# lampada_rev4.net
KiCad netlist of a schematic drawn in EAGLE
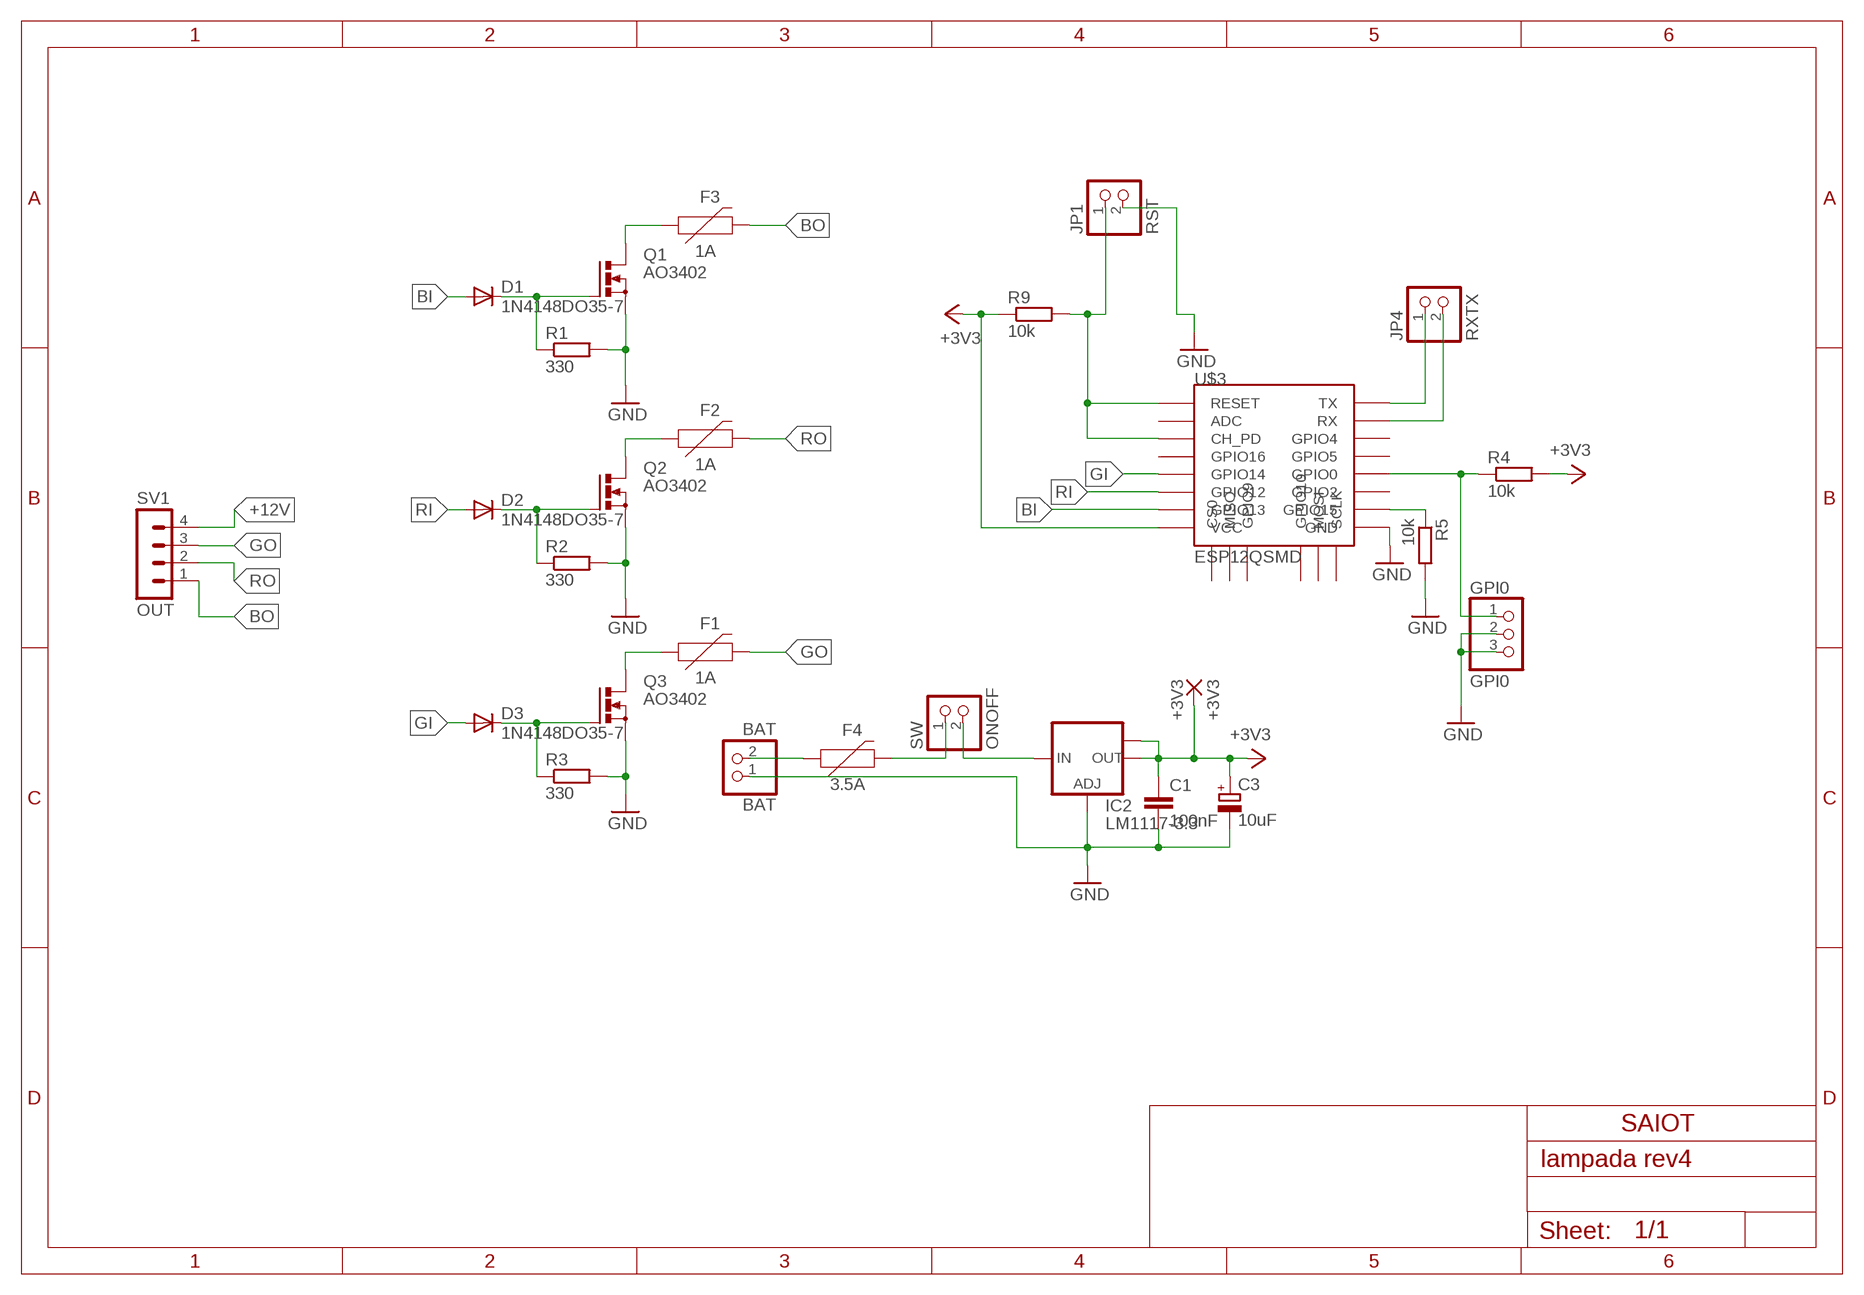
[diagram p0: schematic, sheet 1]

(export (version "E")
  (design (tool "Eeschema 10.0.6"))
  (components
    (comp (ref "+3V3")
      (value "+3V3")
      (footprint "eagle-import:2,15_1,0")
      (libsource (lib "eagle-import") (part "2,15/1,0"))
    )
    (comp (ref "BAT")
      (value "BAT")
      (footprint "eagle-import:1X02")
      (libsource (lib "eagle-import") (part "PINHD-1X2"))
    )
    (comp (ref "C1")
      (value "100nF")
      (footprint "eagle-import:C050-024X044")
      (libsource (lib "eagle-import") (part "C-EU050-024X044"))
    )
    (comp (ref "C3")
      (value "10uF")
      (footprint "eagle-import:E2,5-7")
      (libsource (lib "eagle-import") (part "CPOL-EUE2.5-7"))
    )
    (comp (ref "D1")
      (value "1N4148DO35-7")
      (footprint "eagle-import:DO35-7")
      (libsource (lib "eagle-import") (part "1N4148DO35-7"))
    )
    (comp (ref "D2")
      (value "1N4148DO35-7")
      (footprint "eagle-import:DO35-7")
      (libsource (lib "eagle-import") (part "1N4148DO35-7"))
    )
    (comp (ref "D3")
      (value "1N4148DO35-7")
      (footprint "eagle-import:DO35-7")
      (libsource (lib "eagle-import") (part "1N4148DO35-7"))
    )
    (comp (ref "F1")
      (value "1A")
      (footprint "eagle-import:0805")
      (libsource (lib "eagle-import") (part "PPTC_6V500MA"))
    )
    (comp (ref "F2")
      (value "1A")
      (footprint "eagle-import:0805")
      (libsource (lib "eagle-import") (part "PPTC_6V500MA"))
    )
    (comp (ref "F3")
      (value "1A")
      (footprint "eagle-import:0805")
      (libsource (lib "eagle-import") (part "PPTC_6V500MA"))
    )
    (comp (ref "F4")
      (value "3.5A")
      (footprint "eagle-import:0805")
      (libsource (lib "eagle-import") (part "PPTC_6V500MA"))
    )
    (comp (ref "GPI0")
      (value "GPI0")
      (footprint "eagle-import:1X03")
      (libsource (lib "eagle-import") (part "PINHD-1X3"))
    )
    (comp (ref "IC2")
      (value "LM1117-3.3")
      (footprint "eagle-import:SOT223")
      (libsource (lib "eagle-import") (part "LM1117IMPX-ADJ"))
    )
    (comp (ref "JP1")
      (value "RST")
      (footprint "eagle-import:1X02")
      (libsource (lib "eagle-import") (part "PINHD-1X2"))
    )
    (comp (ref "JP4")
      (value "RXTX")
      (footprint "eagle-import:1X02")
      (libsource (lib "eagle-import") (part "PINHD-1X2"))
    )
    (comp (ref "Q1")
      (value "AO3402")
      (footprint "eagle-import:SOT-23")
      (libsource (lib "eagle-import") (part "IRLML6344"))
    )
    (comp (ref "Q2")
      (value "AO3402")
      (footprint "eagle-import:SOT-23")
      (libsource (lib "eagle-import") (part "IRLML6344"))
    )
    (comp (ref "Q3")
      (value "AO3402")
      (footprint "eagle-import:SOT-23")
      (libsource (lib "eagle-import") (part "IRLML6344"))
    )
    (comp (ref "R1")
      (value "330")
      (footprint "eagle-import:0204_7")
      (libsource (lib "eagle-import") (part "R-EU_0204/7"))
    )
    (comp (ref "R2")
      (value "330")
      (footprint "eagle-import:0204_7")
      (libsource (lib "eagle-import") (part "R-EU_0204/7"))
    )
    (comp (ref "R3")
      (value "330")
      (footprint "eagle-import:0204_7")
      (libsource (lib "eagle-import") (part "R-EU_0204/7"))
    )
    (comp (ref "R4")
      (value "10k")
      (footprint "eagle-import:0204_7")
      (libsource (lib "eagle-import") (part "R-EU_0204/7"))
    )
    (comp (ref "R5")
      (value "10k")
      (footprint "eagle-import:0204_7")
      (libsource (lib "eagle-import") (part "R-EU_0204/7"))
    )
    (comp (ref "R9")
      (value "10k")
      (footprint "eagle-import:0204_7")
      (libsource (lib "eagle-import") (part "R-EU_0204/7"))
    )
    (comp (ref "SV1")
      (value "OUT")
      (footprint "eagle-import:MA04-1")
      (libsource (lib "eagle-import") (part "MA04-1"))
    )
    (comp (ref "SW")
      (value "ONOFF")
      (footprint "eagle-import:1X02")
      (libsource (lib "eagle-import") (part "PINHD-1X2"))
    )
    (comp (ref "U$3")
      (value "ESP12QSMD")
      (footprint "eagle-import:ESP12QSMD")
      (libsource (lib "eagle-import") (part "ESP12QSMD"))
    )
  )
  (nets
    (net (code "1") (name "+3V3") (class "Default")
      (node (ref "+3V3") (pin "1") (pinfunction "P_1") (pintype "passive"))
      (node (ref "C1") (pin "1") (pinfunction "1_1") (pintype "passive"))
      (node (ref "C3") (pin "+") (pinfunction "+_+") (pintype "passive"))
      (node (ref "IC2") (pin "2") (pinfunction "OUT_2") (pintype "passive"))
      (node (ref "IC2") (pin "TAB") (pinfunction "OUT1_TAB") (pintype "passive"))
      (node (ref "R4") (pin "2") (pinfunction "2_2") (pintype "passive"))
      (node (ref "R9") (pin "1") (pinfunction "1_1") (pintype "passive"))
      (node (ref "U$3") (pin "VCC") (pinfunction "VCC_VCC") (pintype "bidirectional"))
    )
    (net (code "2") (name "+12V") (class "Default")
      (node (ref "IC2") (pin "3") (pinfunction "IN_3") (pintype "input"))
      (node (ref "SV1") (pin "4") (pinfunction "4_4") (pintype "passive"))
      (node (ref "SW") (pin "2") (pinfunction "2_2") (pintype "passive"))
    )
    (net (code "3") (name "BI") (class "Default")
      (node (ref "D1") (pin "A") (pinfunction "A_A") (pintype "passive"))
      (node (ref "U$3") (pin "GPIO13") (pinfunction "GPIO13_GPIO13") (pintype "bidirectional"))
    )
    (net (code "4") (name "BO") (class "Default")
      (node (ref "F3") (pin "2") (pinfunction "2_2") (pintype "bidirectional"))
      (node (ref "SV1") (pin "1") (pinfunction "1_1") (pintype "passive"))
    )
    (net (code "5") (name "GI") (class "Default")
      (node (ref "D3") (pin "A") (pinfunction "A_A") (pintype "passive"))
      (node (ref "U$3") (pin "GPIO14") (pinfunction "GPIO14_GPIO14") (pintype "bidirectional"))
    )
    (net (code "6") (name "GND") (class "Default")
      (node (ref "BAT") (pin "1") (pinfunction "1_1") (pintype "passive"))
      (node (ref "C1") (pin "2") (pinfunction "2_2") (pintype "passive"))
      (node (ref "C3") (pin "-") (pinfunction "-_-") (pintype "passive"))
      (node (ref "GPI0") (pin "2") (pinfunction "2_2") (pintype "passive"))
      (node (ref "GPI0") (pin "3") (pinfunction "3_3") (pintype "passive"))
      (node (ref "IC2") (pin "1") (pinfunction "ADJ_1") (pintype "input"))
      (node (ref "JP1") (pin "2") (pinfunction "2_2") (pintype "passive"))
      (node (ref "Q1") (pin "P2") (pinfunction "S_P2") (pintype "passive"))
      (node (ref "Q2") (pin "P2") (pinfunction "S_P2") (pintype "passive"))
      (node (ref "Q3") (pin "P2") (pinfunction "S_P2") (pintype "passive"))
      (node (ref "R1") (pin "2") (pinfunction "2_2") (pintype "passive"))
      (node (ref "R2") (pin "2") (pinfunction "2_2") (pintype "passive"))
      (node (ref "R3") (pin "2") (pinfunction "2_2") (pintype "passive"))
      (node (ref "R5") (pin "2") (pinfunction "2_2") (pintype "passive"))
      (node (ref "U$3") (pin "GND") (pinfunction "GND_GND") (pintype "bidirectional"))
    )
    (net (code "7") (name "GO") (class "Default")
      (node (ref "F1") (pin "2") (pinfunction "2_2") (pintype "bidirectional"))
      (node (ref "SV1") (pin "3") (pinfunction "3_3") (pintype "passive"))
    )
    (net (code "8") (name "Net-(BAT-Pad2)") (class "Default")
      (node (ref "BAT") (pin "2") (pinfunction "2_2") (pintype "passive"))
      (node (ref "F4") (pin "1") (pinfunction "1_1") (pintype "bidirectional"))
    )
    (net (code "9") (name "Net-(F4-Pad2)") (class "Default")
      (node (ref "F4") (pin "2") (pinfunction "2_2") (pintype "bidirectional"))
      (node (ref "SW") (pin "1") (pinfunction "1_1") (pintype "passive"))
    )
    (net (code "10") (name "Net-(GPI0-Pad1)") (class "Default")
      (node (ref "GPI0") (pin "1") (pinfunction "1_1") (pintype "passive"))
      (node (ref "R4") (pin "1") (pinfunction "1_1") (pintype "passive"))
      (node (ref "U$3") (pin "GPIO0") (pinfunction "GPIO0_GPIO0") (pintype "bidirectional"))
    )
    (net (code "11") (name "Net-(JP1-Pad1)") (class "Default")
      (node (ref "JP1") (pin "1") (pinfunction "1_1") (pintype "passive"))
      (node (ref "R9") (pin "2") (pinfunction "2_2") (pintype "passive"))
      (node (ref "U$3") (pin "CH_PD") (pinfunction "CH_PD_CH_PD") (pintype "bidirectional"))
      (node (ref "U$3") (pin "RESET") (pinfunction "RESET_RESET") (pintype "bidirectional"))
    )
    (net (code "12") (name "Net-(JP4-Pad1)") (class "Default")
      (node (ref "JP4") (pin "1") (pinfunction "1_1") (pintype "passive"))
      (node (ref "U$3") (pin "TX") (pinfunction "TX_TX") (pintype "bidirectional"))
    )
    (net (code "13") (name "Net-(JP4-Pad2)") (class "Default")
      (node (ref "JP4") (pin "2") (pinfunction "2_2") (pintype "passive"))
      (node (ref "U$3") (pin "RX") (pinfunction "RX_RX") (pintype "bidirectional"))
    )
    (net (code "14") (name "Net-(Q1-D)") (class "Default")
      (node (ref "F3") (pin "1") (pinfunction "1_1") (pintype "bidirectional"))
      (node (ref "Q1") (pin "P3") (pinfunction "D_P3") (pintype "passive"))
    )
    (net (code "15") (name "Net-(Q1-G)") (class "Default")
      (node (ref "D1") (pin "C") (pinfunction "C_C") (pintype "passive"))
      (node (ref "Q1") (pin "P1") (pinfunction "G_P1") (pintype "passive"))
      (node (ref "R1") (pin "1") (pinfunction "1_1") (pintype "passive"))
    )
    (net (code "16") (name "Net-(Q2-D)") (class "Default")
      (node (ref "F2") (pin "1") (pinfunction "1_1") (pintype "bidirectional"))
      (node (ref "Q2") (pin "P3") (pinfunction "D_P3") (pintype "passive"))
    )
    (net (code "17") (name "Net-(Q2-G)") (class "Default")
      (node (ref "D2") (pin "C") (pinfunction "C_C") (pintype "passive"))
      (node (ref "Q2") (pin "P1") (pinfunction "G_P1") (pintype "passive"))
      (node (ref "R2") (pin "1") (pinfunction "1_1") (pintype "passive"))
    )
    (net (code "18") (name "Net-(Q3-D)") (class "Default")
      (node (ref "F1") (pin "1") (pinfunction "1_1") (pintype "bidirectional"))
      (node (ref "Q3") (pin "P3") (pinfunction "D_P3") (pintype "passive"))
    )
    (net (code "19") (name "Net-(Q3-G)") (class "Default")
      (node (ref "D3") (pin "C") (pinfunction "C_C") (pintype "passive"))
      (node (ref "Q3") (pin "P1") (pinfunction "G_P1") (pintype "passive"))
      (node (ref "R3") (pin "1") (pinfunction "1_1") (pintype "passive"))
    )
    (net (code "20") (name "Net-(R5-Pad1)") (class "Default")
      (node (ref "R5") (pin "1") (pinfunction "1_1") (pintype "passive"))
      (node (ref "U$3") (pin "GPIO15") (pinfunction "GPIO15_GPIO15") (pintype "bidirectional"))
    )
    (net (code "21") (name "RI") (class "Default")
      (node (ref "D2") (pin "A") (pinfunction "A_A") (pintype "passive"))
      (node (ref "U$3") (pin "GPIO12") (pinfunction "GPIO12_GPIO12") (pintype "bidirectional"))
    )
    (net (code "22") (name "RO") (class "Default")
      (node (ref "F2") (pin "2") (pinfunction "2_2") (pintype "bidirectional"))
      (node (ref "SV1") (pin "2") (pinfunction "2_2") (pintype "passive"))
    )
    (net (code "23") (name "unconnected-(U$3-PadADC)") (class "Default")
      (node (ref "U$3") (pin "ADC") (pinfunction "ADC_ADC") (pintype "bidirectional"))
    )
    (net (code "24") (name "unconnected-(U$3-PadCS0)") (class "Default")
      (node (ref "U$3") (pin "CS0") (pinfunction "CS0_CS0") (pintype "bidirectional"))
    )
    (net (code "25") (name "unconnected-(U$3-PadGPIO2)") (class "Default")
      (node (ref "U$3") (pin "GPIO2") (pinfunction "GPIO2_GPIO2") (pintype "bidirectional"))
    )
    (net (code "26") (name "unconnected-(U$3-PadGPIO4)") (class "Default")
      (node (ref "U$3") (pin "GPIO4") (pinfunction "GPIO4_GPIO4") (pintype "bidirectional"))
    )
    (net (code "27") (name "unconnected-(U$3-PadGPIO5)") (class "Default")
      (node (ref "U$3") (pin "GPIO5") (pinfunction "GPIO5_GPIO5") (pintype "bidirectional"))
    )
    (net (code "28") (name "unconnected-(U$3-PadGPIO9)") (class "Default")
      (node (ref "U$3") (pin "GPIO9") (pinfunction "GPIO9_GPIO9") (pintype "bidirectional"))
    )
    (net (code "29") (name "unconnected-(U$3-PadGPIO10)") (class "Default")
      (node (ref "U$3") (pin "GPIO10") (pinfunction "GPIO10_GPIO10") (pintype "bidirectional"))
    )
    (net (code "30") (name "unconnected-(U$3-PadGPIO16)") (class "Default")
      (node (ref "U$3") (pin "GPIO16") (pinfunction "GPIO16_GPIO16") (pintype "bidirectional"))
    )
    (net (code "31") (name "unconnected-(U$3-PadMISO)") (class "Default")
      (node (ref "U$3") (pin "MISO") (pinfunction "MISO_MISO") (pintype "bidirectional"))
    )
    (net (code "32") (name "unconnected-(U$3-PadMOSI)") (class "Default")
      (node (ref "U$3") (pin "MOSI") (pinfunction "MOSI_MOSI") (pintype "bidirectional"))
    )
    (net (code "33") (name "unconnected-(U$3-PadSCLK)") (class "Default")
      (node (ref "U$3") (pin "SCLK") (pinfunction "SCLK_SCLK") (pintype "bidirectional"))
    )
  )
)
